# midi_in.net
KiCad netlist of a schematic drawn in EAGLE
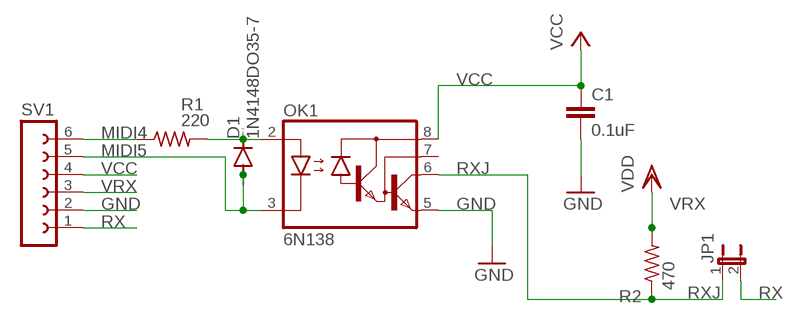
[diagram p0: schematic, sheet 1]

(export (version "E")
  (design (tool "Eeschema 10.0.6"))
  (components
    (comp (ref "C1")
      (value "0.1uF")
      (footprint "eagle-import:C10B5")
      (libsource (lib "eagle-import") (part "C10/5"))
    )
    (comp (ref "D1")
      (value "1N4148DO35-7")
      (footprint "eagle-import:DO35-7")
      (libsource (lib "eagle-import") (part "1N4148DO35-7"))
    )
    (comp (ref "JP1")
      (value "JP1E")
      (footprint "eagle-import:JP1")
      (libsource (lib "eagle-import") (part "JP1E"))
    )
    (comp (ref "OK1")
      (value "6N138")
      (footprint "eagle-import:DIL08")
      (fields (field (name "MF") "VISHAY/TELEFUNKEN"))
      (libsource (lib "eagle-import") (part "6N138"))
    )
    (comp (ref "R1")
      (value "220")
      (footprint "eagle-import:0207_10")
      (libsource (lib "eagle-import") (part "R-US_0207/10"))
    )
    (comp (ref "R2")
      (value "470")
      (footprint "eagle-import:0207_10")
      (libsource (lib "eagle-import") (part "R-US_0207/10"))
    )
    (comp (ref "SV1")
      (value "FE06-1")
      (footprint "eagle-import:FE06")
      (libsource (lib "eagle-import") (part "FE06-1"))
    )
  )
  (nets
    (net (code "1") (name "/MIDI4") (class "Default")
      (node (ref "R1") (pin "1") (pinfunction "1_1") (pintype "passive"))
      (node (ref "SV1") (pin "6") (pinfunction "6_6") (pintype "passive"))
    )
    (net (code "2") (name "/MIDI5") (class "Default")
      (node (ref "D1") (pin "A") (pinfunction "A_A") (pintype "passive"))
      (node (ref "OK1") (pin "3") (pinfunction "C_3") (pintype "passive"))
      (node (ref "SV1") (pin "5") (pinfunction "5_5") (pintype "passive"))
    )
    (net (code "3") (name "/RX") (class "Default")
      (node (ref "JP1") (pin "2") (pinfunction "2_2") (pintype "passive"))
      (node (ref "SV1") (pin "1") (pinfunction "1_1") (pintype "passive"))
    )
    (net (code "4") (name "/RXJ") (class "Default")
      (node (ref "JP1") (pin "1") (pinfunction "1_1") (pintype "passive"))
      (node (ref "OK1") (pin "6") (pinfunction "VO_6") (pintype "passive"))
      (node (ref "R2") (pin "1") (pinfunction "1_1") (pintype "passive"))
    )
    (net (code "5") (name "GND") (class "Default")
      (node (ref "C1") (pin "2") (pinfunction "2_2") (pintype "passive"))
      (node (ref "OK1") (pin "5") (pinfunction "GND_5") (pintype "passive"))
      (node (ref "SV1") (pin "2") (pinfunction "2_2") (pintype "passive"))
    )
    (net (code "6") (name "Net-(OK1-A)") (class "Default")
      (node (ref "D1") (pin "C") (pinfunction "C_C") (pintype "passive"))
      (node (ref "OK1") (pin "2") (pinfunction "A_2") (pintype "passive"))
      (node (ref "R1") (pin "2") (pinfunction "2_2") (pintype "passive"))
    )
    (net (code "7") (name "VCC") (class "Default")
      (node (ref "C1") (pin "1") (pinfunction "1_1") (pintype "passive"))
      (node (ref "OK1") (pin "8") (pinfunction "VCC_8") (pintype "passive"))
      (node (ref "SV1") (pin "4") (pinfunction "4_4") (pintype "passive"))
    )
    (net (code "8") (name "VDD") (class "Default")
      (node (ref "R2") (pin "2") (pinfunction "2_2") (pintype "passive"))
      (node (ref "SV1") (pin "3") (pinfunction "3_3") (pintype "passive"))
    )
    (net (code "9") (name "unconnected-(OK1-VB-Pad7)") (class "Default")
      (node (ref "OK1") (pin "7") (pinfunction "VB_7") (pintype "passive"))
    )
  )
)
